# GPS_lte.net
KiCad netlist of a schematic drawn in Altium Designer
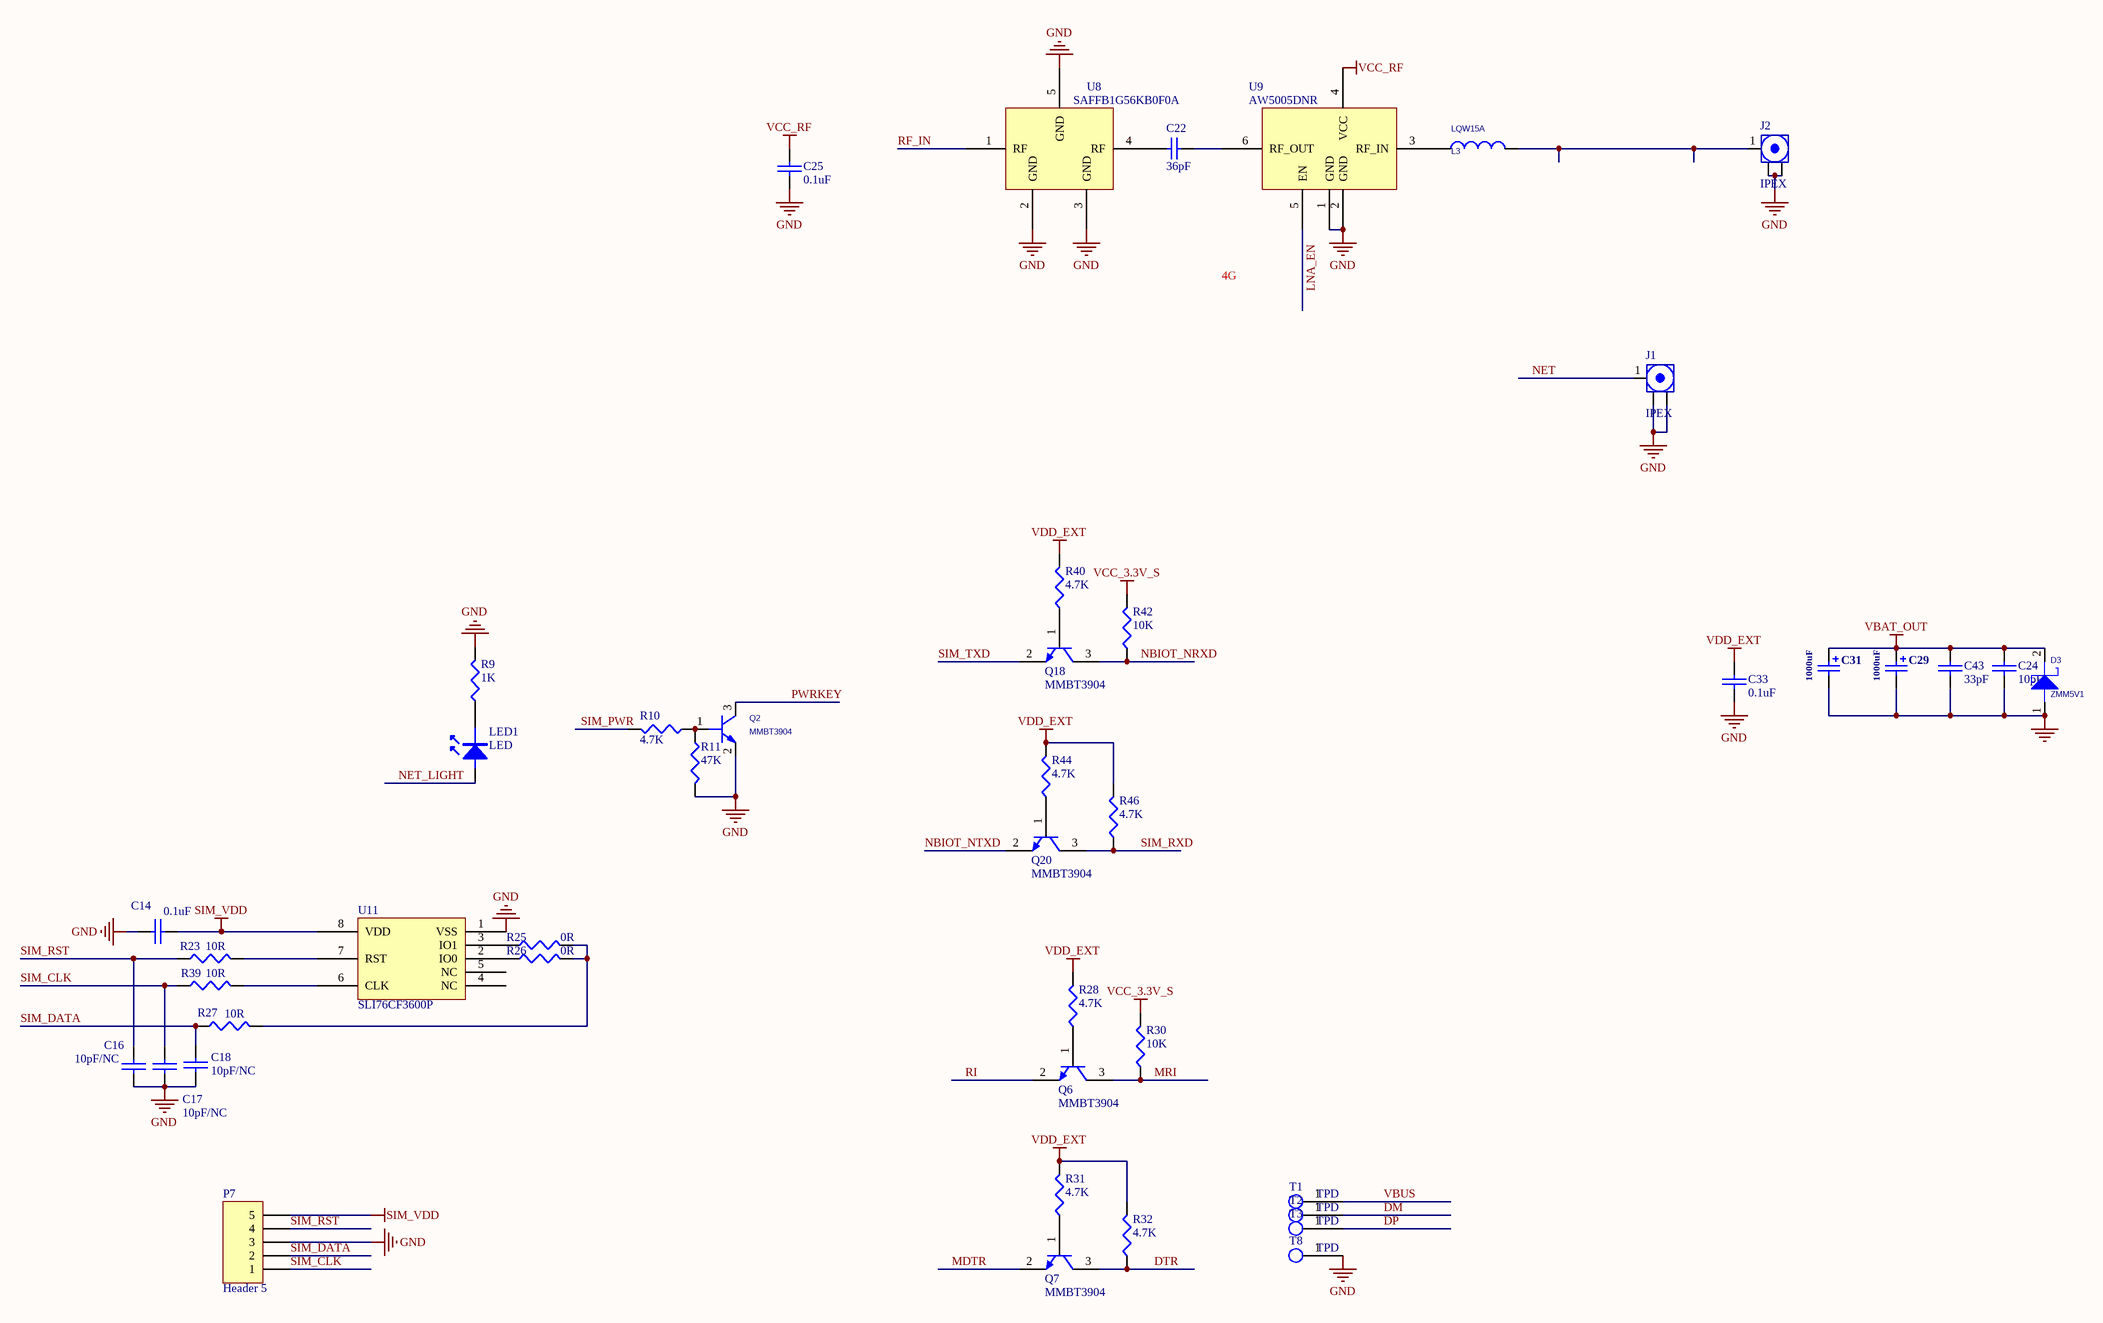
[diagram p0: GPS&&lte.SchDoc]

(export (version "E")
  (design (tool "Eeschema 10.0.6"))
  (components
    (comp (ref "C14")
      (value "0.1uF")
      (footprint "0402C")
      (description "Capacitor")
      (libsource (lib "ZWLIntegrated_Library") (part "CAP"))
    )
    (comp (ref "C16")
      (value "10pF/NC")
      (footprint "0402C")
      (description "Capacitor")
      (libsource (lib "ZWLIntegrated_Library") (part "CAP"))
    )
    (comp (ref "C17")
      (value "10pF/NC")
      (footprint "0402C")
      (description "Capacitor")
      (libsource (lib "ZWLIntegrated_Library") (part "CAP"))
    )
    (comp (ref "C18")
      (value "10pF/NC")
      (footprint "0402C")
      (description "Capacitor")
      (libsource (lib "ZWLIntegrated_Library") (part "CAP"))
    )
    (comp (ref "C22")
      (value "36pF")
      (footprint "0402c")
      (description "Capacitor")
      (fields (field (name "PUBLISHER") "Altium Limited"))
      (libsource (lib "Miscellaneous Devices") (part "Cap"))
    )
    (comp (ref "C24")
      (value "10pF")
      (footprint "0402C")
      (description "Capacitor")
      (libsource (lib "ZWLIntegrated_Library") (part "CAP"))
    )
    (comp (ref "C25")
      (value "0.1uF")
      (footprint "0402C")
      (description "Capacitor")
      (libsource (lib "ZWLIntegrated_Library") (part "CAP"))
    )
    (comp (ref "C29")
      (value "1000uF")
      (footprint "7343")
      (description "Polarized Capacitor (Surface Mount)")
      (libsource (lib "KT_iBeacon") (part "Cap Pol3"))
    )
    (comp (ref "C31")
      (value "1000uF")
      (footprint "7343")
      (description "Polarized Capacitor (Surface Mount)")
      (libsource (lib "KT_iBeacon") (part "Cap Pol3"))
    )
    (comp (ref "C33")
      (value "0.1uF")
      (footprint "0402C")
      (description "Capacitor")
      (libsource (lib "ZWLIntegrated_Library") (part "CAP"))
    )
    (comp (ref "C43")
      (value "33pF")
      (footprint "0402C")
      (description "Capacitor")
      (libsource (lib "ZWLIntegrated_Library") (part "CAP"))
    )
    (comp (ref "D3")
      (value "ZMM5V1")
      (footprint "LL-34(D1206)")
      (fields (field (name "Comment") "DIODE_SCHOTTKY_0"))
      (libsource (lib "KT_iBeacon") (part "DIODE_SCHOTTKY_0"))
    )
    (comp (ref "J1") (value "IPEX") (footprint "RF-UFL") (libsource (lib "我的元件库") (part "ANT")))
    (comp (ref "J2") (value "IPEX") (footprint "RF-UFL") (libsource (lib "我的元件库") (part "ANT")))
    (comp (ref "L3") (value "LQW15A") (footprint "0402R") (libsource (lib "*") (part "INDUCTOR_1")))
    (comp (ref "LED1") (value "LED") (footprint "0603LED") (libsource (lib "我的元件库") (part "LED")))
    (comp (ref "P7")
      (value "Header 5")
      (footprint "5×1.25mmSMT")
      (description "Header, 5-Pin")
      (fields (field (name "PUBLISHER") "Altium Limited"))
      (libsource (lib "Miscellaneous Connectors") (part "Header 5"))
    )
    (comp (ref "Q2") (value "MMBT3904") (footprint "SOT23-3") (libsource (lib "*") (part "2N1069_1")))
    (comp (ref "Q6") (value "MMBT3904") (footprint "SOT23-3") (libsource (lib "Schlib1") (part "NPN")))
    (comp (ref "Q7") (value "MMBT3904") (footprint "SOT23-3") (libsource (lib "Schlib1") (part "NPN")))
    (comp (ref "Q18") (value "MMBT3904") (footprint "SOT23-3") (libsource (lib "Schlib1") (part "NPN")))
    (comp (ref "Q20") (value "MMBT3904") (footprint "SOT23-3") (libsource (lib "Schlib1") (part "NPN")))
    (comp (ref "R9") (value "1K") (footprint "0402R") (libsource (lib "ZWLIntegrated_Library") (part "RES1")))
    (comp (ref "R10")
      (value "4.7K")
      (footprint "0402R")
      (libsource (lib "ZWLIntegrated_Library") (part "RES1"))
    )
    (comp (ref "R11")
      (value "47K")
      (footprint "0402R")
      (libsource (lib "ZWLIntegrated_Library") (part "RES1"))
    )
    (comp (ref "R23")
      (value "10R")
      (footprint "0402R")
      (libsource (lib "ZWLIntegrated_Library") (part "RES1"))
    )
    (comp (ref "R25")
      (value "0R")
      (footprint "0402R")
      (libsource (lib "ZWLIntegrated_Library") (part "RES1"))
    )
    (comp (ref "R26")
      (value "0R")
      (footprint "0402R")
      (libsource (lib "ZWLIntegrated_Library") (part "RES1"))
    )
    (comp (ref "R27")
      (value "10R")
      (footprint "0402R")
      (libsource (lib "ZWLIntegrated_Library") (part "RES1"))
    )
    (comp (ref "R28")
      (value "4.7K")
      (footprint "0402R")
      (libsource (lib "ZWLIntegrated_Library") (part "RES1"))
    )
    (comp (ref "R30")
      (value "10K")
      (footprint "0402R")
      (libsource (lib "ZWLIntegrated_Library") (part "RES1"))
    )
    (comp (ref "R31")
      (value "4.7K")
      (footprint "0402R")
      (libsource (lib "ZWLIntegrated_Library") (part "RES1"))
    )
    (comp (ref "R32")
      (value "4.7K")
      (footprint "0402R")
      (libsource (lib "ZWLIntegrated_Library") (part "RES1"))
    )
    (comp (ref "R39")
      (value "10R")
      (footprint "0402R")
      (libsource (lib "ZWLIntegrated_Library") (part "RES1"))
    )
    (comp (ref "R40")
      (value "4.7K")
      (footprint "0402R")
      (libsource (lib "ZWLIntegrated_Library") (part "RES1"))
    )
    (comp (ref "R42")
      (value "10K")
      (footprint "0402R")
      (libsource (lib "ZWLIntegrated_Library") (part "RES1"))
    )
    (comp (ref "R44")
      (value "4.7K")
      (footprint "0402R")
      (libsource (lib "ZWLIntegrated_Library") (part "RES1"))
    )
    (comp (ref "R46")
      (value "4.7K")
      (footprint "0402R")
      (libsource (lib "ZWLIntegrated_Library") (part "RES1"))
    )
    (comp (ref "T1") (value "TPD") (footprint "TPD") (libsource (lib "stm32") (part "TPD")))
    (comp (ref "T2") (value "TPD") (footprint "TPD") (libsource (lib "stm32") (part "TPD")))
    (comp (ref "T3") (value "TPD") (footprint "TPD") (libsource (lib "stm32") (part "TPD")))
    (comp (ref "T8") (value "TPD") (footprint "TPD") (libsource (lib "stm32") (part "TPD")))
    (comp (ref "U8")
      (value "SAFFB1G56KB0F0A")
      (footprint "SAFFB1G56KB0F0A")
      (libsource (lib "stm32") (part "SAFFB1G56KBOFA"))
    )
    (comp (ref "U9") (value "AW5005DNR") (footprint "AW5005") (libsource (lib "stm32") (part "AW5005DNR")))
    (comp (ref "U11")
      (value "SLI76CF3600P")
      (footprint "QFN127P500X600X80-8N")
      (libsource (lib "stm32") (part "SLI76CF3600P"))
    )
  )
  (nets
    (net (code "1") (name "/DM") (class "Default") (node (ref "T2") (pin "1") (pintype "passive")))
    (net (code "2") (name "/DP") (class "Default") (node (ref "T3") (pin "1") (pintype "passive")))
    (net (code "3") (name "/DTR") (class "Default")
      (node (ref "Q7") (pin "3") (pinfunction "C_3") (pintype "passive"))
      (node (ref "R32") (pin "1") (pinfunction "1_1") (pintype "passive"))
    )
    (net (code "4") (name "/LNA_EN") (class "Default")
      (node (ref "U9") (pin "5") (pinfunction "EN_5") (pintype "passive"))
    )
    (net (code "5") (name "/MDTR") (class "Default")
      (node (ref "Q7") (pin "2") (pinfunction "E_2") (pintype "passive"))
    )
    (net (code "6") (name "/MRI") (class "Default")
      (node (ref "Q6") (pin "3") (pinfunction "C_3") (pintype "passive"))
      (node (ref "R30") (pin "1") (pinfunction "1_1") (pintype "passive"))
    )
    (net (code "7") (name "/NBIOT_NRXD") (class "Default")
      (node (ref "Q18") (pin "3") (pinfunction "C_3") (pintype "passive"))
      (node (ref "R42") (pin "1") (pinfunction "1_1") (pintype "passive"))
    )
    (net (code "8") (name "/NBIOT_NTXD") (class "Default")
      (node (ref "Q20") (pin "2") (pinfunction "E_2") (pintype "passive"))
    )
    (net (code "9") (name "/NET") (class "Default")
      (node (ref "J1") (pin "1") (pinfunction "X_1") (pintype "passive"))
    )
    (net (code "10") (name "/NET_LIGHT") (class "Default")
      (node (ref "LED1") (pin "1") (pinfunction "1_1") (pintype "passive"))
    )
    (net (code "11") (name "/PWRKEY") (class "Default")
      (node (ref "Q2") (pin "3") (pinfunction "C_3") (pintype "passive"))
    )
    (net (code "12") (name "/RF_IN") (class "Default")
      (node (ref "U8") (pin "1") (pinfunction "RF_1") (pintype "passive"))
    )
    (net (code "13") (name "/RI") (class "Default")
      (node (ref "Q6") (pin "2") (pinfunction "E_2") (pintype "passive"))
    )
    (net (code "14") (name "/SIM_CLK") (class "Default")
      (node (ref "C17") (pin "2") (pinfunction "2_2") (pintype "passive"))
      (node (ref "P7") (pin "1") (pinfunction "1_1") (pintype "passive"))
      (node (ref "R39") (pin "1") (pinfunction "1_1") (pintype "passive"))
    )
    (net (code "15") (name "/SIM_DATA") (class "Default")
      (node (ref "C18") (pin "2") (pinfunction "2_2") (pintype "passive"))
      (node (ref "P7") (pin "2") (pinfunction "2_2") (pintype "passive"))
      (node (ref "R27") (pin "1") (pinfunction "1_1") (pintype "passive"))
    )
    (net (code "16") (name "/SIM_PWR") (class "Default")
      (node (ref "R10") (pin "2") (pinfunction "2_2") (pintype "passive"))
    )
    (net (code "17") (name "/SIM_RST") (class "Default")
      (node (ref "C16") (pin "2") (pinfunction "2_2") (pintype "passive"))
      (node (ref "P7") (pin "4") (pinfunction "4_4") (pintype "passive"))
      (node (ref "R23") (pin "1") (pinfunction "1_1") (pintype "passive"))
    )
    (net (code "18") (name "/SIM_RXD") (class "Default")
      (node (ref "Q20") (pin "3") (pinfunction "C_3") (pintype "passive"))
      (node (ref "R46") (pin "1") (pinfunction "1_1") (pintype "passive"))
    )
    (net (code "19") (name "/SIM_TXD") (class "Default")
      (node (ref "Q18") (pin "2") (pinfunction "E_2") (pintype "passive"))
    )
    (net (code "20") (name "/VBUS") (class "Default") (node (ref "T1") (pin "1") (pintype "passive")))
    (net (code "21") (name "GND") (class "Default")
      (node (ref "C14") (pin "1") (pinfunction "1_1") (pintype "passive"))
      (node (ref "C16") (pin "1") (pinfunction "1_1") (pintype "passive"))
      (node (ref "C17") (pin "1") (pinfunction "1_1") (pintype "passive"))
      (node (ref "C18") (pin "1") (pinfunction "1_1") (pintype "passive"))
      (node (ref "C24") (pin "1") (pinfunction "1_1") (pintype "passive"))
      (node (ref "C25") (pin "1") (pinfunction "1_1") (pintype "passive"))
      (node (ref "C29") (pin "2") (pinfunction "2_2") (pintype "passive"))
      (node (ref "C31") (pin "2") (pinfunction "2_2") (pintype "passive"))
      (node (ref "C33") (pin "1") (pinfunction "1_1") (pintype "passive"))
      (node (ref "C43") (pin "1") (pinfunction "1_1") (pintype "passive"))
      (node (ref "D3") (pin "1") (pinfunction "1_1") (pintype "passive"))
      (node (ref "J1") (pin "2") (pinfunction "Y_2") (pintype "passive"))
      (node (ref "J2") (pin "2") (pinfunction "Y_2") (pintype "passive"))
      (node (ref "P7") (pin "3") (pinfunction "3_3") (pintype "passive"))
      (node (ref "Q2") (pin "2") (pinfunction "E_2") (pintype "passive"))
      (node (ref "R11") (pin "2") (pinfunction "2_2") (pintype "passive"))
      (node (ref "R9") (pin "2") (pinfunction "2_2") (pintype "passive"))
      (node (ref "T8") (pin "1") (pintype "passive"))
      (node (ref "U11") (pin "1") (pinfunction "VSS_1") (pintype "passive"))
      (node (ref "U8") (pin "2") (pinfunction "GND_2") (pintype "passive"))
      (node (ref "U8") (pin "3") (pinfunction "GND_3") (pintype "passive"))
      (node (ref "U8") (pin "5") (pinfunction "GND_5") (pintype "passive"))
      (node (ref "U9") (pin "1") (pinfunction "GND_1") (pintype "passive"))
      (node (ref "U9") (pin "2") (pinfunction "GND_2") (pintype "passive"))
    )
    (net (code "22") (name "Net-(C22-Pad1)") (class "Default")
      (node (ref "C22") (pin "1") (pinfunction "1_1") (pintype "passive"))
      (node (ref "U8") (pin "4") (pinfunction "RF_4") (pintype "passive"))
    )
    (net (code "23") (name "Net-(J2-X)") (class "Default")
      (node (ref "J2") (pin "1") (pinfunction "X_1") (pintype "passive"))
      (node (ref "L3") (pin "2") (pinfunction "2_2") (pintype "passive"))
    )
    (net (code "24") (name "Net-(LED1-Pad2)") (class "Default")
      (node (ref "LED1") (pin "2") (pinfunction "2_2") (pintype "passive"))
      (node (ref "R9") (pin "1") (pinfunction "1_1") (pintype "passive"))
    )
    (net (code "25") (name "Net-(Q2-B)") (class "Default")
      (node (ref "Q2") (pin "1") (pinfunction "B_1") (pintype "passive"))
      (node (ref "R10") (pin "1") (pinfunction "1_1") (pintype "passive"))
      (node (ref "R11") (pin "1") (pinfunction "1_1") (pintype "passive"))
    )
    (net (code "26") (name "Net-(Q6-B)") (class "Default")
      (node (ref "Q6") (pin "1") (pinfunction "B_1") (pintype "passive"))
      (node (ref "R28") (pin "1") (pinfunction "1_1") (pintype "passive"))
    )
    (net (code "27") (name "Net-(Q7-B)") (class "Default")
      (node (ref "Q7") (pin "1") (pinfunction "B_1") (pintype "passive"))
      (node (ref "R31") (pin "1") (pinfunction "1_1") (pintype "passive"))
    )
    (net (code "28") (name "Net-(Q18-B)") (class "Default")
      (node (ref "Q18") (pin "1") (pinfunction "B_1") (pintype "passive"))
      (node (ref "R40") (pin "1") (pinfunction "1_1") (pintype "passive"))
    )
    (net (code "29") (name "Net-(Q20-B)") (class "Default")
      (node (ref "Q20") (pin "1") (pinfunction "B_1") (pintype "passive"))
      (node (ref "R44") (pin "1") (pinfunction "1_1") (pintype "passive"))
    )
    (net (code "30") (name "Net-(R25-Pad2)") (class "Default")
      (node (ref "R25") (pin "2") (pinfunction "2_2") (pintype "passive"))
      (node (ref "R26") (pin "2") (pinfunction "2_2") (pintype "passive"))
      (node (ref "R27") (pin "2") (pinfunction "2_2") (pintype "passive"))
    )
    (net (code "31") (name "Net-(U9-RF_IN)") (class "Default")
      (node (ref "L3") (pin "1") (pinfunction "1_1") (pintype "passive"))
      (node (ref "U9") (pin "3") (pinfunction "RF_IN_3") (pintype "passive"))
    )
    (net (code "32") (name "Net-(U9-RF_OUT)") (class "Default")
      (node (ref "C22") (pin "2") (pinfunction "2_2") (pintype "passive"))
      (node (ref "U9") (pin "6") (pinfunction "RF_OUT_6") (pintype "passive"))
    )
    (net (code "33") (name "Net-(U11-CLK)") (class "Default")
      (node (ref "R39") (pin "2") (pinfunction "2_2") (pintype "passive"))
      (node (ref "U11") (pin "6") (pinfunction "CLK_6") (pintype "passive"))
    )
    (net (code "34") (name "Net-(U11-IO0)") (class "Default")
      (node (ref "R26") (pin "1") (pinfunction "1_1") (pintype "passive"))
      (node (ref "U11") (pin "2") (pinfunction "IO0_2") (pintype "passive"))
    )
    (net (code "35") (name "Net-(U11-IO1)") (class "Default")
      (node (ref "R25") (pin "1") (pinfunction "1_1") (pintype "passive"))
      (node (ref "U11") (pin "3") (pinfunction "IO1_3") (pintype "passive"))
    )
    (net (code "36") (name "Net-(U11-RST)") (class "Default")
      (node (ref "R23") (pin "2") (pinfunction "2_2") (pintype "passive"))
      (node (ref "U11") (pin "7") (pinfunction "RST_7") (pintype "passive"))
    )
    (net (code "37") (name "SIM_VDD") (class "Default")
      (node (ref "C14") (pin "2") (pinfunction "2_2") (pintype "passive"))
      (node (ref "P7") (pin "5") (pinfunction "5_5") (pintype "passive"))
      (node (ref "U11") (pin "8") (pinfunction "VDD_8") (pintype "passive"))
    )
    (net (code "38") (name "VBAT_OUT") (class "Default")
      (node (ref "C24") (pin "2") (pinfunction "2_2") (pintype "passive"))
      (node (ref "C29") (pin "1") (pinfunction "1_1") (pintype "passive"))
      (node (ref "C31") (pin "1") (pinfunction "1_1") (pintype "passive"))
      (node (ref "C43") (pin "2") (pinfunction "2_2") (pintype "passive"))
      (node (ref "D3") (pin "2") (pinfunction "2_2") (pintype "passive"))
    )
    (net (code "39") (name "VCC_3.3V_S") (class "Default")
      (node (ref "R30") (pin "2") (pinfunction "2_2") (pintype "passive"))
      (node (ref "R42") (pin "2") (pinfunction "2_2") (pintype "passive"))
    )
    (net (code "40") (name "VCC_RF") (class "Default")
      (node (ref "C25") (pin "2") (pinfunction "2_2") (pintype "passive"))
      (node (ref "U9") (pin "4") (pinfunction "VCC_4") (pintype "passive"))
    )
    (net (code "41") (name "VDD_EXT") (class "Default")
      (node (ref "C33") (pin "2") (pinfunction "2_2") (pintype "passive"))
      (node (ref "R28") (pin "2") (pinfunction "2_2") (pintype "passive"))
      (node (ref "R31") (pin "2") (pinfunction "2_2") (pintype "passive"))
      (node (ref "R32") (pin "2") (pinfunction "2_2") (pintype "passive"))
      (node (ref "R40") (pin "2") (pinfunction "2_2") (pintype "passive"))
      (node (ref "R44") (pin "2") (pinfunction "2_2") (pintype "passive"))
      (node (ref "R46") (pin "2") (pinfunction "2_2") (pintype "passive"))
    )
    (net (code "42") (name "unconnected-(U11-NC-Pad4)") (class "Default")
      (node (ref "U11") (pin "4") (pinfunction "NC_4") (pintype "passive"))
    )
    (net (code "43") (name "unconnected-(U11-NC-Pad5)") (class "Default")
      (node (ref "U11") (pin "5") (pinfunction "NC_5") (pintype "passive"))
    )
  )
)
